# wireless-sensor-node.net
KiCad netlist of a schematic drawn in EAGLE
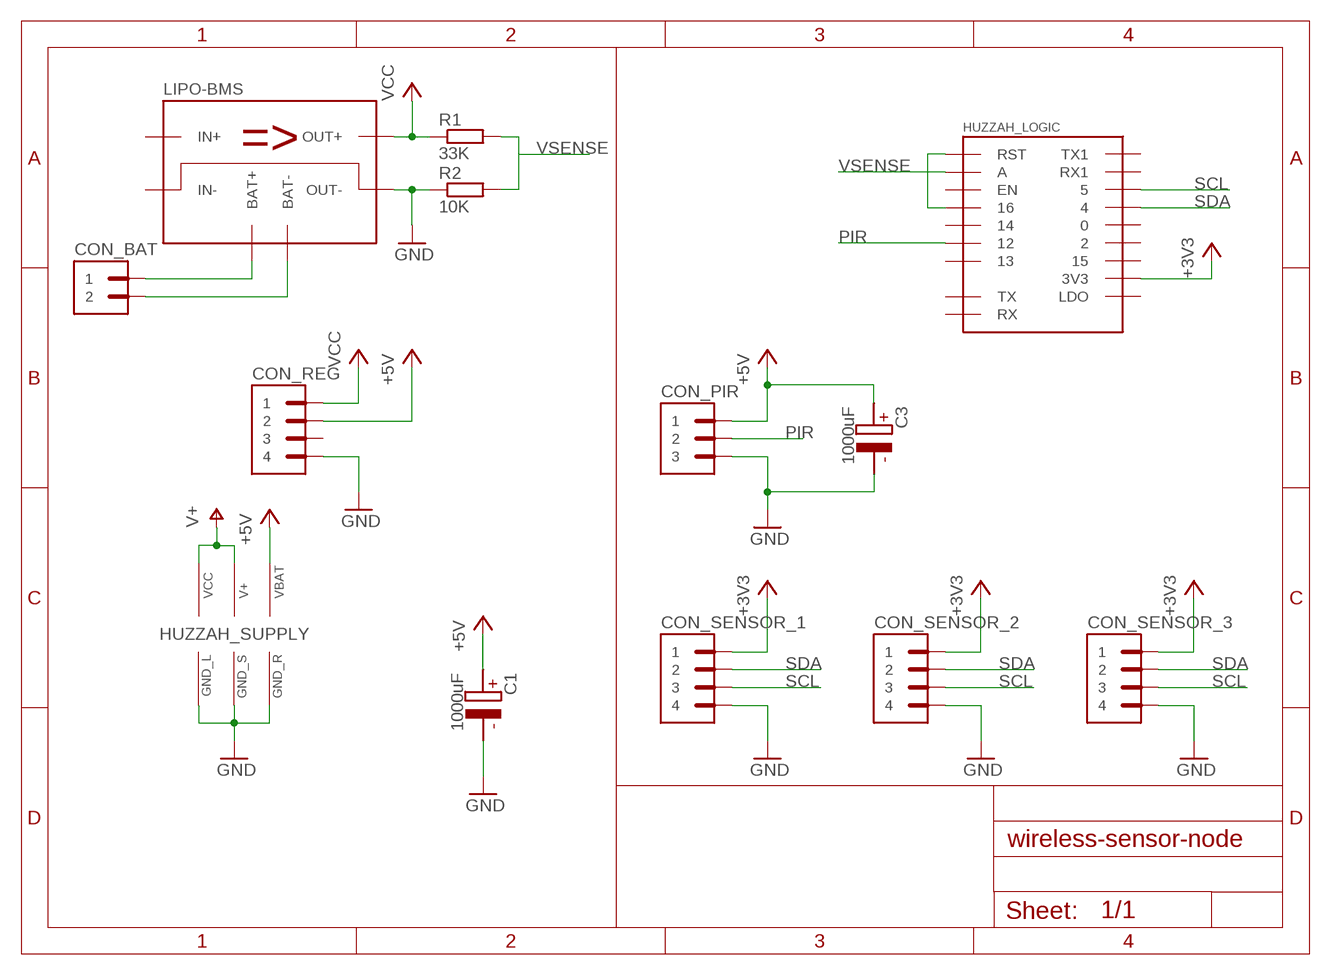
[diagram p0: schematic, sheet 1]

(export (version "E")
  (design (tool "Eeschema 10.0.6"))
  (components
    (comp (ref "C1")
      (value "1000uF")
      (footprint "eagle-import:CAP_POL_10X13_5")
      (libsource (lib "eagle-import") (part "CAPACITOR_POLARIZED-10X13-5.0"))
    )
    (comp (ref "C3")
      (value "1000uF")
      (footprint "eagle-import:CAP_POL_10X13_5")
      (libsource (lib "eagle-import") (part "CAPACITOR_POLARIZED-10X13-5.0"))
    )
    (comp (ref "CON_BAT")
      (value "PIN_HEADER_2-WIDE")
      (footprint "eagle-import:BREAKAWAY_STRAIGHT_2_WIDE")
      (libsource (lib "eagle-import") (part "PIN_HEADER_2-WIDE"))
    )
    (comp (ref "CON_PIR")
      (value "PIN_HEADER_3-WIDE")
      (footprint "eagle-import:BREAKAWAY_STRAIGHT_3_WIDE")
      (libsource (lib "eagle-import") (part "PIN_HEADER_3-WIDE"))
    )
    (comp (ref "CON_REG")
      (value "PIN_HEADER_4-WIDE")
      (footprint "eagle-import:BREAKAWAY_STRAIGHT_4_WIDE")
      (libsource (lib "eagle-import") (part "PIN_HEADER_4-WIDE"))
    )
    (comp (ref "CON_SENSOR_1")
      (value "PIN_HEADER_4-WIDE")
      (footprint "eagle-import:BREAKAWAY_STRAIGHT_4_WIDE")
      (libsource (lib "eagle-import") (part "PIN_HEADER_4-WIDE"))
    )
    (comp (ref "CON_SENSOR_2")
      (value "PIN_HEADER_4-WIDE")
      (footprint "eagle-import:BREAKAWAY_STRAIGHT_4_WIDE")
      (libsource (lib "eagle-import") (part "PIN_HEADER_4-WIDE"))
    )
    (comp (ref "CON_SENSOR_3")
      (value "PIN_HEADER_4-WIDE")
      (footprint "eagle-import:BREAKAWAY_STRAIGHT_4_WIDE")
      (libsource (lib "eagle-import") (part "PIN_HEADER_4-WIDE"))
    )
    (comp (ref "HUZZAH")
      (value "ADAFRUIT_HUZZAH-THT-NM")
      (footprint "eagle-import:ADAFRUIT_HUZZAH_NO_MOUNTS")
      (libsource (lib "eagle-import") (part "ADAFRUIT_HUZZAH-THT-NM"))
    )
    (comp (ref "LIPO-BMS")
      (value "LIPO-BMS-CHARGER-MODULE")
      (footprint "eagle-import:LIPO-BMS-CHARGER")
      (libsource (lib "eagle-import") (part "LIPO-BMS-CHARGER-MODULE"))
    )
    (comp (ref "R1")
      (value "33K")
      (footprint "eagle-import:RESISTOR-1_4W-AXIAL")
      (libsource (lib "eagle-import") (part "RESISTOR-1/4W-12.7-AXIAL"))
    )
    (comp (ref "R2")
      (value "10K")
      (footprint "eagle-import:RESISTOR-1_4W-AXIAL")
      (libsource (lib "eagle-import") (part "RESISTOR-1/4W-12.7-AXIAL"))
    )
  )
  (nets
    (net (code "1") (name "+3V3") (class "Default")
      (node (ref "CON_SENSOR_1") (pin "1") (pinfunction "1_1") (pintype "bidirectional"))
      (node (ref "CON_SENSOR_2") (pin "1") (pinfunction "1_1") (pintype "bidirectional"))
      (node (ref "CON_SENSOR_3") (pin "1") (pinfunction "1_1") (pintype "bidirectional"))
      (node (ref "HUZZAH") (pin "3.3V") (pinfunction "3V3_3.3V") (pintype "power_in"))
    )
    (net (code "2") (name "+5V") (class "Default")
      (node (ref "C1") (pin "A") (pinfunction "A_A") (pintype "passive"))
      (node (ref "C3") (pin "A") (pinfunction "A_A") (pintype "passive"))
      (node (ref "CON_PIR") (pin "1") (pinfunction "1_1") (pintype "bidirectional"))
      (node (ref "CON_REG") (pin "2") (pinfunction "2_2") (pintype "bidirectional"))
      (node (ref "HUZZAH") (pin "VBAT") (pinfunction "VBAT_VBAT") (pintype "power_in"))
    )
    (net (code "3") (name "/IN+") (class "Default")
      (node (ref "LIPO-BMS") (pin "IN+") (pinfunction "IN+_IN+") (pintype "power_in"))
    )
    (net (code "4") (name "/IN-") (class "Default")
      (node (ref "LIPO-BMS") (pin "IN-") (pinfunction "IN-_IN-") (pintype "power_in"))
    )
    (net (code "5") (name "/PIR") (class "Default")
      (node (ref "CON_PIR") (pin "2") (pinfunction "2_2") (pintype "bidirectional"))
      (node (ref "HUZZAH") (pin "12") (pinfunction "12_12") (pintype "bidirectional"))
    )
    (net (code "6") (name "/SCL") (class "Default")
      (node (ref "CON_SENSOR_1") (pin "3") (pinfunction "3_3") (pintype "bidirectional"))
      (node (ref "CON_SENSOR_2") (pin "3") (pinfunction "3_3") (pintype "bidirectional"))
      (node (ref "CON_SENSOR_3") (pin "3") (pinfunction "3_3") (pintype "bidirectional"))
      (node (ref "HUZZAH") (pin "5") (pinfunction "5_5") (pintype "bidirectional"))
    )
    (net (code "7") (name "/SDA") (class "Default")
      (node (ref "CON_SENSOR_1") (pin "2") (pinfunction "2_2") (pintype "bidirectional"))
      (node (ref "CON_SENSOR_2") (pin "2") (pinfunction "2_2") (pintype "bidirectional"))
      (node (ref "CON_SENSOR_3") (pin "2") (pinfunction "2_2") (pintype "bidirectional"))
      (node (ref "HUZZAH") (pin "4") (pinfunction "4_4") (pintype "bidirectional"))
    )
    (net (code "8") (name "/VSENSE") (class "Default")
      (node (ref "HUZZAH") (pin "A") (pinfunction "A_A") (pintype "bidirectional"))
      (node (ref "R1") (pin "P$2") (pinfunction "2_P$2") (pintype "passive"))
      (node (ref "R2") (pin "P$2") (pinfunction "2_P$2") (pintype "passive"))
    )
    (net (code "9") (name "GND") (class "Default")
      (node (ref "C1") (pin "C") (pinfunction "C_C") (pintype "passive"))
      (node (ref "C3") (pin "C") (pinfunction "C_C") (pintype "passive"))
      (node (ref "CON_PIR") (pin "3") (pinfunction "3_3") (pintype "bidirectional"))
      (node (ref "CON_REG") (pin "4") (pinfunction "4_4") (pintype "bidirectional"))
      (node (ref "CON_SENSOR_1") (pin "4") (pinfunction "4_4") (pintype "bidirectional"))
      (node (ref "CON_SENSOR_2") (pin "4") (pinfunction "4_4") (pintype "bidirectional"))
      (node (ref "CON_SENSOR_3") (pin "4") (pinfunction "4_4") (pintype "bidirectional"))
      (node (ref "HUZZAH") (pin "GND_L") (pinfunction "GND_L_GND_L") (pintype "power_in"))
      (node (ref "HUZZAH") (pin "GND_R") (pinfunction "GND_R_GND_R") (pintype "power_in"))
      (node (ref "HUZZAH") (pin "GND_S") (pinfunction "GND_S_GND_S") (pintype "power_in"))
      (node (ref "LIPO-BMS") (pin "OUT-") (pinfunction "OUT-_OUT-") (pintype "power_in"))
      (node (ref "R2") (pin "P$1") (pinfunction "1_P$1") (pintype "passive"))
    )
    (net (code "10") (name "Net-(CON_BAT-Pad1)") (class "Default")
      (node (ref "CON_BAT") (pin "1") (pinfunction "1_1") (pintype "bidirectional"))
      (node (ref "LIPO-BMS") (pin "BAT+") (pinfunction "BAT+_BAT+") (pintype "power_in"))
    )
    (net (code "11") (name "Net-(CON_BAT-Pad2)") (class "Default")
      (node (ref "CON_BAT") (pin "2") (pinfunction "2_2") (pintype "bidirectional"))
      (node (ref "LIPO-BMS") (pin "BAT-") (pinfunction "BAT-_BAT-") (pintype "power_in"))
    )
    (net (code "12") (name "Net-(HUZZAH-Pad16)") (class "Default")
      (node (ref "HUZZAH") (pin "16") (pinfunction "16_16") (pintype "bidirectional"))
      (node (ref "HUZZAH") (pin "RST") (pinfunction "RST_RST") (pintype "input"))
    )
    (net (code "13") (name "V+") (class "Default")
      (node (ref "HUZZAH") (pin "V+") (pinfunction "V+_V+") (pintype "power_in"))
      (node (ref "HUZZAH") (pin "VCC") (pinfunction "VCC_VCC") (pintype "power_in"))
    )
    (net (code "14") (name "VCC") (class "Default")
      (node (ref "CON_REG") (pin "1") (pinfunction "1_1") (pintype "bidirectional"))
      (node (ref "LIPO-BMS") (pin "OUT+") (pinfunction "OUT+_OUT+") (pintype "power_in"))
      (node (ref "R1") (pin "P$1") (pinfunction "1_P$1") (pintype "passive"))
    )
    (net (code "15") (name "unconnected-(CON_REG-Pad3)") (class "Default")
      (node (ref "CON_REG") (pin "3") (pinfunction "3_3") (pintype "bidirectional"))
    )
    (net (code "16") (name "unconnected-(HUZZAH-Pad0)") (class "Default")
      (node (ref "HUZZAH") (pin "0") (pinfunction "0_0") (pintype "bidirectional"))
    )
    (net (code "17") (name "unconnected-(HUZZAH-Pad2)") (class "Default")
      (node (ref "HUZZAH") (pin "2") (pinfunction "2_2") (pintype "bidirectional"))
    )
    (net (code "18") (name "unconnected-(HUZZAH-Pad13)") (class "Default")
      (node (ref "HUZZAH") (pin "13") (pinfunction "13_13") (pintype "bidirectional"))
    )
    (net (code "19") (name "unconnected-(HUZZAH-Pad14)") (class "Default")
      (node (ref "HUZZAH") (pin "14") (pinfunction "14_14") (pintype "bidirectional"))
    )
    (net (code "20") (name "unconnected-(HUZZAH-Pad15)") (class "Default")
      (node (ref "HUZZAH") (pin "15") (pinfunction "15_15") (pintype "bidirectional"))
    )
    (net (code "21") (name "unconnected-(HUZZAH-PadEN)") (class "Default")
      (node (ref "HUZZAH") (pin "EN") (pinfunction "EN_EN") (pintype "input"))
    )
    (net (code "22") (name "unconnected-(HUZZAH-PadLDO)") (class "Default")
      (node (ref "HUZZAH") (pin "LDO") (pinfunction "LDO_LDO") (pintype "bidirectional"))
    )
    (net (code "23") (name "unconnected-(HUZZAH-PadRX)") (class "Default")
      (node (ref "HUZZAH") (pin "RX") (pinfunction "RX_RX") (pintype "input"))
    )
    (net (code "24") (name "unconnected-(HUZZAH-PadTX)") (class "Default")
      (node (ref "HUZZAH") (pin "TX") (pinfunction "TX_TX") (pintype "output"))
    )
    (net (code "25") (name "unconnected-(HUZZAHA-RX1-PadRX_1)") (class "Default")
      (node (ref "HUZZAH") (pin "RX_1") (pinfunction "RX1_RX_1") (pintype "input"))
    )
    (net (code "26") (name "unconnected-(HUZZAHA-TX1-PadTX_1)") (class "Default")
      (node (ref "HUZZAH") (pin "TX_1") (pinfunction "TX1_TX_1") (pintype "output"))
    )
  )
)
